# display.net
KiCad netlist of a schematic drawn in Altium Designer
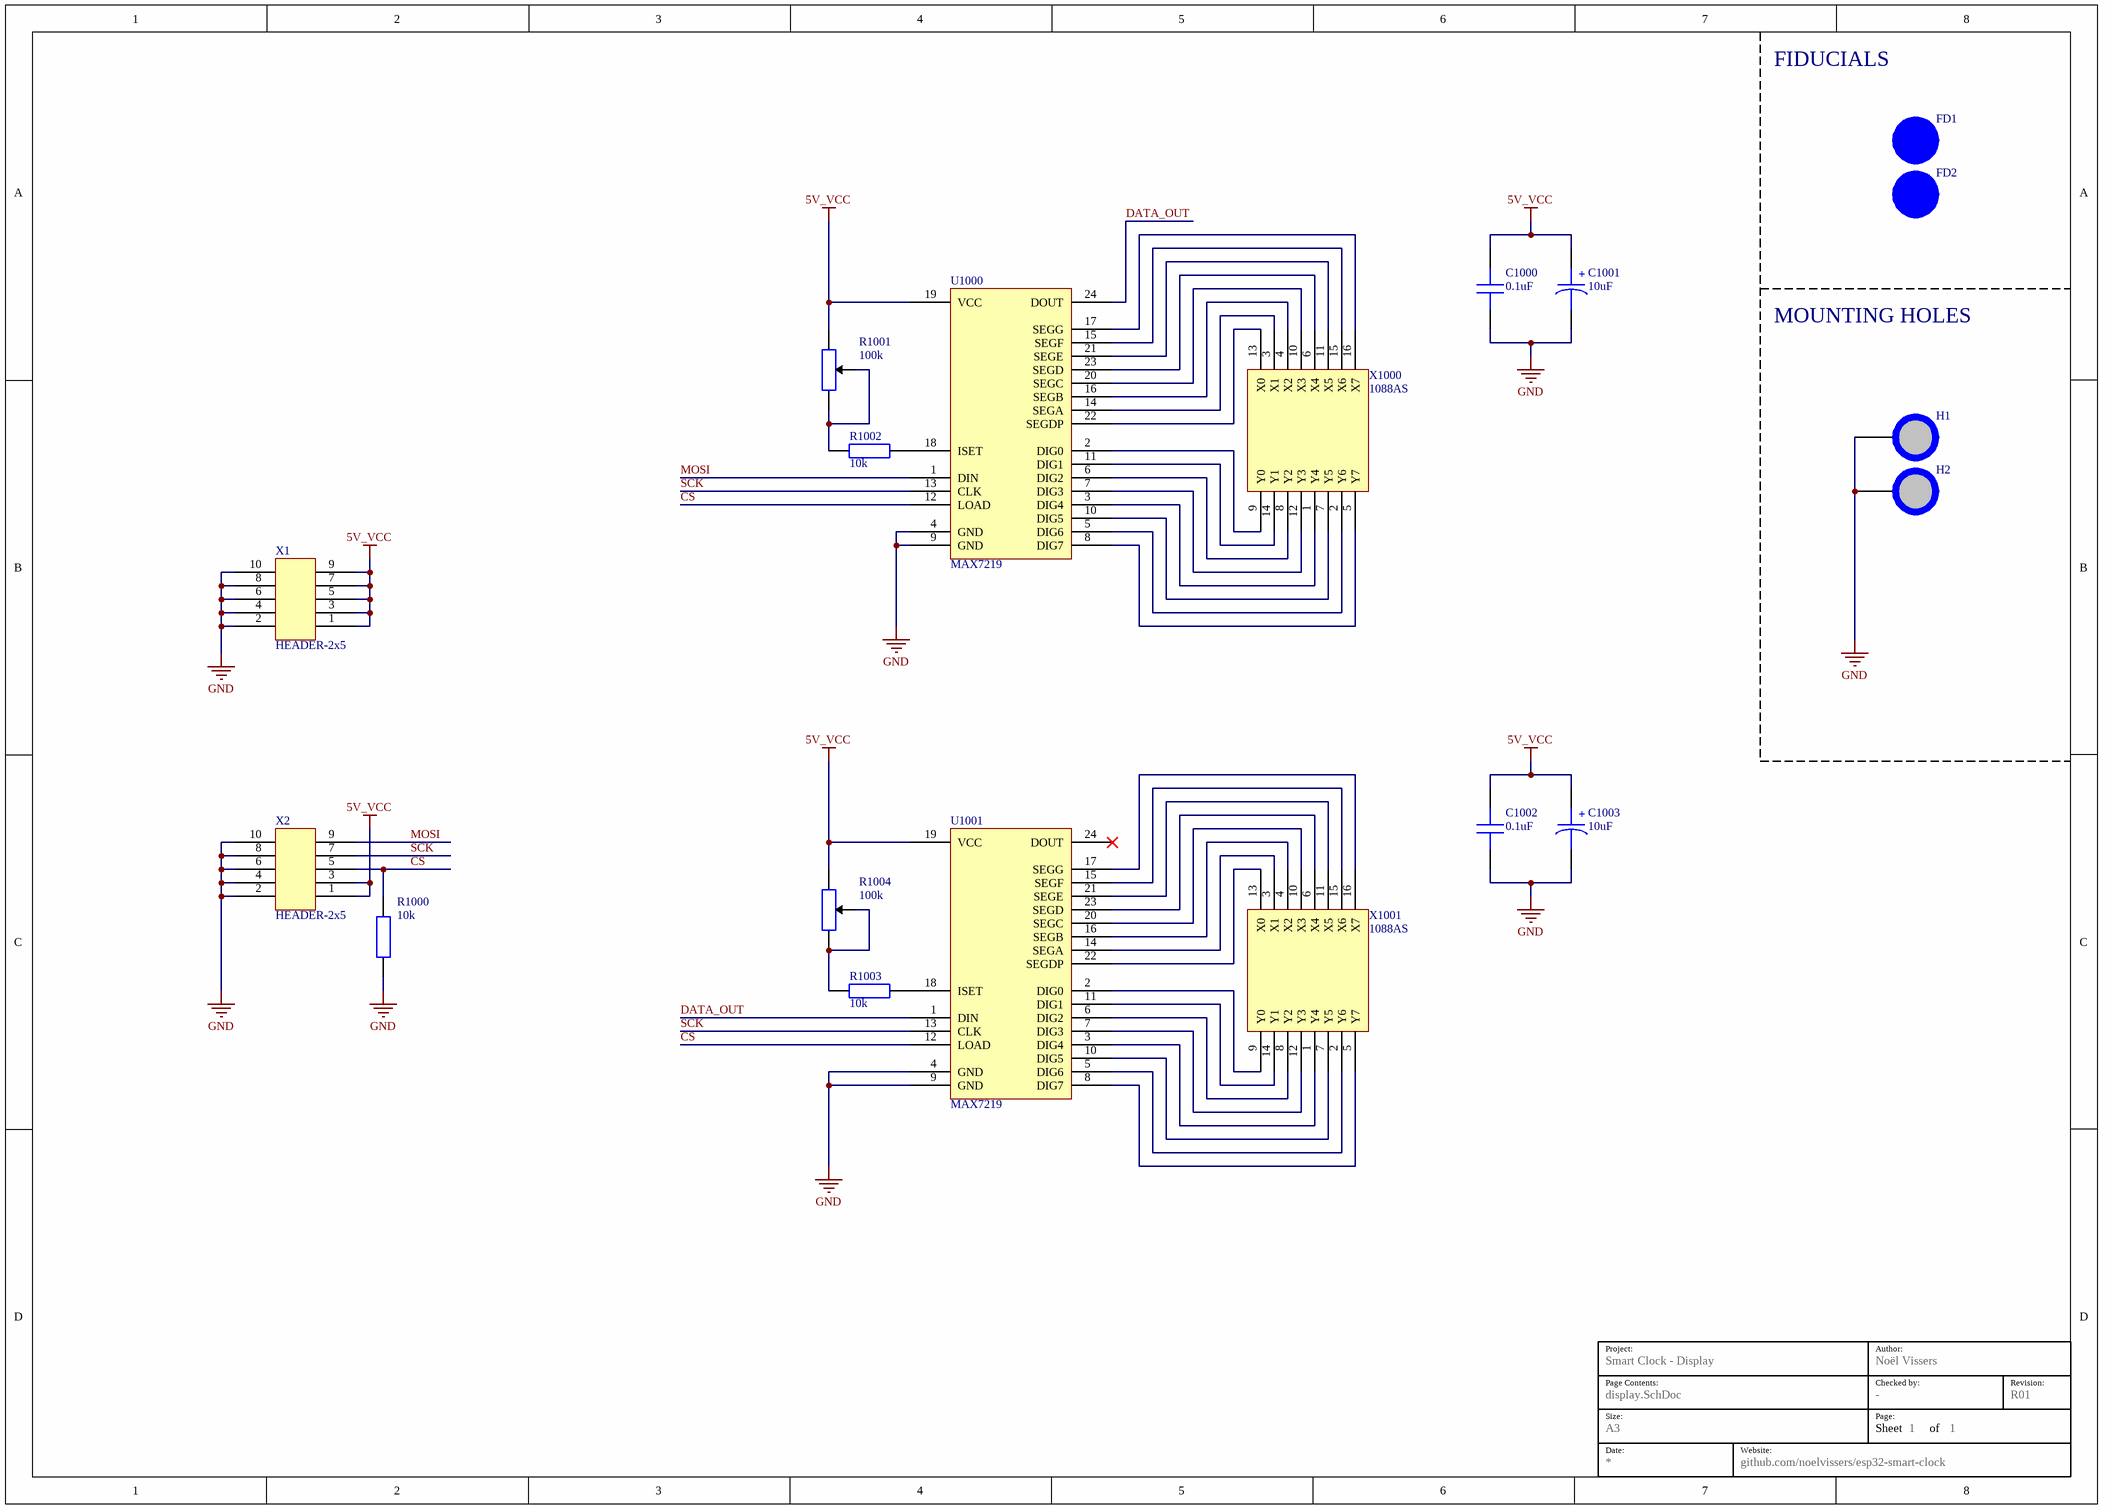
[diagram p0: display.SchDoc]

(export (version "E")
  (design (tool "Eeschema 10.0.6"))
  (components
    (comp (ref "*")
      (value "TITLE BLOCK")
      (fields (field (name "SIZE") "A3"))
      (libsource (lib "smart-clock-lib") (part "TITLE BLOCK"))
    )
    (comp (ref "C1000")
      (value "0.1uF")
      (footprint "TH-CAPACITOR - ANGLE")
      (description "GENERIC CAPACITOR")
      (libsource (lib "smart-clock-lib") (part "CAPACITOR"))
    )
    (comp (ref "C1001")
      (value "10uF")
      (footprint "TH-CAPACITOR - POL - ANGLE")
      (description "POLARIZED CAPACITOR")
      (libsource (lib "smart-clock-lib") (part "CAPACITOR POL"))
    )
    (comp (ref "C1002")
      (value "0.1uF")
      (footprint "TH-CAPACITOR - ANGLE")
      (description "GENERIC CAPACITOR")
      (libsource (lib "smart-clock-lib") (part "CAPACITOR"))
    )
    (comp (ref "C1003")
      (value "10uF")
      (footprint "TH-CAPACITOR - POL - ANGLE")
      (description "POLARIZED CAPACITOR")
      (libsource (lib "smart-clock-lib") (part "CAPACITOR POL"))
    )
    (comp (ref "FD1")
      (value "FD")
      (footprint "FD")
      (description "FIDUCIAL MARKER")
      (libsource (lib "smart-clock-lib") (part "FD"))
    )
    (comp (ref "FD2")
      (value "FD")
      (footprint "FD")
      (description "FIDUCIAL MARKER")
      (libsource (lib "smart-clock-lib") (part "FD"))
    )
    (comp (ref "H1")
      (value "SIZE")
      (footprint "HOLE")
      (description "M3 MOUNTING HOLE WITH SCREW AND SPACER")
      (libsource (lib "smart-clock-lib") (part "MOUNTING-HOLE"))
    )
    (comp (ref "H2")
      (value "SIZE")
      (footprint "HOLE")
      (description "M3 MOUNTING HOLE WITH SCREW AND SPACER")
      (libsource (lib "smart-clock-lib") (part "MOUNTING-HOLE"))
    )
    (comp (ref "R1000")
      (value "10k")
      (footprint "AXIAL RESISTOR")
      (description "GENERIC RESISTOR")
      (libsource (lib "") (part "RESISTOR_1"))
    )
    (comp (ref "R1001")
      (value "100k")
      (footprint "POTENTIOMETER")
      (description "POTMETER")
      (libsource (lib "smart-clock-lib") (part "POTMETER"))
    )
    (comp (ref "R1002")
      (value "10k")
      (footprint "AXIAL RESISTOR")
      (description "GENERIC RESISTOR")
      (libsource (lib "smart-clock-lib") (part "RESISTOR"))
    )
    (comp (ref "R1003")
      (value "10k")
      (footprint "AXIAL RESISTOR")
      (description "GENERIC RESISTOR")
      (libsource (lib "smart-clock-lib") (part "RESISTOR"))
    )
    (comp (ref "R1004")
      (value "100k")
      (footprint "POTENTIOMETER")
      (description "POTMETER")
      (libsource (lib "smart-clock-lib") (part "POTMETER"))
    )
    (comp (ref "U1000")
      (value "MAX7219")
      (footprint "DIP-24 WITH SOCKET")
      (description "IC DRVR 7 SEGMNT 8 DIGIT 24SOIC")
      (fields
        (field (name "MF") "Maxim Integrated")
        (field (name "DIGI-KEY_PART_NUMBER") "MAX7219CWG+TCT-ND")
      )
      (libsource (lib "smart-clock-lib") (part "MAX7219"))
    )
    (comp (ref "U1001")
      (value "MAX7219")
      (footprint "DIP-24 WITH SOCKET")
      (description "IC DRVR 7 SEGMNT 8 DIGIT 24SOIC")
      (fields
        (field (name "MF") "Maxim Integrated")
        (field (name "DIGI-KEY_PART_NUMBER") "MAX7219CWG+TCT-ND")
      )
      (libsource (lib "smart-clock-lib") (part "MAX7219"))
    )
    (comp (ref "X1")
      (value "HEADER-2x5")
      (footprint "HEADER-2x5-MALE")
      (description "2.54mm HEADER 2x5")
      (libsource (lib "smart-clock-lib") (part "HEADER-2x5"))
    )
    (comp (ref "X2")
      (value "HEADER-2x5")
      (footprint "HEADER-2x5-MALE")
      (description "2.54mm HEADER 2x5")
      (libsource (lib "smart-clock-lib") (part "HEADER-2x5"))
    )
    (comp (ref "X1000")
      (value "1088AS")
      (footprint "1088AS-DOT-MATRIX-8x8")
      (description "8x8 DOT MATRIX LED DISPLAY")
      (libsource (lib "smart-clock-lib") (part "1088AS-DOT-MATRIX"))
    )
    (comp (ref "X1001")
      (value "1088AS")
      (footprint "1088AS-DOT-MATRIX-8x8")
      (description "8x8 DOT MATRIX LED DISPLAY")
      (libsource (lib "smart-clock-lib") (part "1088AS-DOT-MATRIX"))
    )
  )
  (nets
    (net (code "1") (name "/CS") (class "Default")
      (node (ref "R1000") (pin "1") (pinfunction "1_1") (pintype "passive"))
      (node (ref "U1000") (pin "12") (pinfunction "LOAD_12") (pintype "passive"))
      (node (ref "U1001") (pin "12") (pinfunction "LOAD_12") (pintype "passive"))
      (node (ref "X2") (pin "5") (pinfunction "5_5") (pintype "passive"))
    )
    (net (code "2") (name "/DATA_OUT") (class "Default")
      (node (ref "U1000") (pin "24") (pinfunction "DOUT_24") (pintype "passive"))
      (node (ref "U1001") (pin "1") (pinfunction "DIN_1") (pintype "passive"))
    )
    (net (code "3") (name "/MOSI") (class "Default")
      (node (ref "U1000") (pin "1") (pinfunction "DIN_1") (pintype "passive"))
      (node (ref "X2") (pin "9") (pinfunction "9_9") (pintype "passive"))
    )
    (net (code "4") (name "/SCK") (class "Default")
      (node (ref "U1000") (pin "13") (pinfunction "CLK_13") (pintype "passive"))
      (node (ref "U1001") (pin "13") (pinfunction "CLK_13") (pintype "passive"))
      (node (ref "X2") (pin "7") (pinfunction "7_7") (pintype "passive"))
    )
    (net (code "5") (name "5V_VCC") (class "Default")
      (node (ref "C1000") (pin "1") (pinfunction "1_1") (pintype "passive"))
      (node (ref "C1001") (pin "2") (pinfunction "2_2") (pintype "passive"))
      (node (ref "C1002") (pin "1") (pinfunction "1_1") (pintype "passive"))
      (node (ref "C1003") (pin "2") (pinfunction "2_2") (pintype "passive"))
      (node (ref "R1001") (pin "1") (pinfunction "1_1") (pintype "passive"))
      (node (ref "R1004") (pin "1") (pinfunction "1_1") (pintype "passive"))
      (node (ref "U1000") (pin "19") (pinfunction "VCC_19") (pintype "passive"))
      (node (ref "U1001") (pin "19") (pinfunction "VCC_19") (pintype "passive"))
      (node (ref "X1") (pin "1") (pinfunction "1_1") (pintype "passive"))
      (node (ref "X1") (pin "3") (pinfunction "3_3") (pintype "passive"))
      (node (ref "X1") (pin "5") (pinfunction "5_5") (pintype "passive"))
      (node (ref "X1") (pin "7") (pinfunction "7_7") (pintype "passive"))
      (node (ref "X1") (pin "9") (pinfunction "9_9") (pintype "passive"))
      (node (ref "X2") (pin "1") (pinfunction "1_1") (pintype "passive"))
      (node (ref "X2") (pin "3") (pinfunction "3_3") (pintype "passive"))
    )
    (net (code "6") (name "GND") (class "Default")
      (node (ref "C1000") (pin "2") (pinfunction "2_2") (pintype "passive"))
      (node (ref "C1001") (pin "1") (pinfunction "1_1") (pintype "passive"))
      (node (ref "C1002") (pin "2") (pinfunction "2_2") (pintype "passive"))
      (node (ref "C1003") (pin "1") (pinfunction "1_1") (pintype "passive"))
      (node (ref "H1") (pin "1") (pintype "passive"))
      (node (ref "H2") (pin "1") (pintype "passive"))
      (node (ref "R1000") (pin "2") (pinfunction "2_2") (pintype "passive"))
      (node (ref "U1000") (pin "4") (pinfunction "GND_4") (pintype "passive"))
      (node (ref "U1000") (pin "9") (pinfunction "GND_9") (pintype "passive"))
      (node (ref "U1001") (pin "4") (pinfunction "GND_4") (pintype "passive"))
      (node (ref "U1001") (pin "9") (pinfunction "GND_9") (pintype "passive"))
      (node (ref "X1") (pin "10") (pinfunction "10_10") (pintype "passive"))
      (node (ref "X1") (pin "2") (pinfunction "2_2") (pintype "passive"))
      (node (ref "X1") (pin "4") (pinfunction "4_4") (pintype "passive"))
      (node (ref "X1") (pin "6") (pinfunction "6_6") (pintype "passive"))
      (node (ref "X1") (pin "8") (pinfunction "8_8") (pintype "passive"))
      (node (ref "X2") (pin "10") (pinfunction "10_10") (pintype "passive"))
      (node (ref "X2") (pin "2") (pinfunction "2_2") (pintype "passive"))
      (node (ref "X2") (pin "4") (pinfunction "4_4") (pintype "passive"))
      (node (ref "X2") (pin "6") (pinfunction "6_6") (pintype "passive"))
      (node (ref "X2") (pin "8") (pinfunction "8_8") (pintype "passive"))
    )
    (net (code "7") (name "Net-(R1001-Pad2)") (class "Default")
      (node (ref "R1001") (pin "2") (pinfunction "2_2") (pintype "passive"))
      (node (ref "R1001") (pin "3") (pinfunction "3_3") (pintype "passive"))
      (node (ref "R1002") (pin "1") (pinfunction "1_1") (pintype "passive"))
    )
    (net (code "8") (name "Net-(R1003-Pad1)") (class "Default")
      (node (ref "R1003") (pin "1") (pinfunction "1_1") (pintype "passive"))
      (node (ref "R1004") (pin "2") (pinfunction "2_2") (pintype "passive"))
      (node (ref "R1004") (pin "3") (pinfunction "3_3") (pintype "passive"))
    )
    (net (code "9") (name "Net-(U1000-DIG0)") (class "Default")
      (node (ref "U1000") (pin "2") (pinfunction "DIG0_2") (pintype "passive"))
      (node (ref "X1000") (pin "9") (pinfunction "Y0_9") (pintype "passive"))
    )
    (net (code "10") (name "Net-(U1000-DIG1)") (class "Default")
      (node (ref "U1000") (pin "11") (pinfunction "DIG1_11") (pintype "passive"))
      (node (ref "X1000") (pin "14") (pinfunction "Y1_14") (pintype "passive"))
    )
    (net (code "11") (name "Net-(U1000-DIG2)") (class "Default")
      (node (ref "U1000") (pin "6") (pinfunction "DIG2_6") (pintype "passive"))
      (node (ref "X1000") (pin "8") (pinfunction "Y2_8") (pintype "passive"))
    )
    (net (code "12") (name "Net-(U1000-DIG3)") (class "Default")
      (node (ref "U1000") (pin "7") (pinfunction "DIG3_7") (pintype "passive"))
      (node (ref "X1000") (pin "12") (pinfunction "Y3_12") (pintype "passive"))
    )
    (net (code "13") (name "Net-(U1000-DIG4)") (class "Default")
      (node (ref "U1000") (pin "3") (pinfunction "DIG4_3") (pintype "passive"))
      (node (ref "X1000") (pin "1") (pinfunction "Y4_1") (pintype "passive"))
    )
    (net (code "14") (name "Net-(U1000-DIG5)") (class "Default")
      (node (ref "U1000") (pin "10") (pinfunction "DIG5_10") (pintype "passive"))
      (node (ref "X1000") (pin "7") (pinfunction "Y5_7") (pintype "passive"))
    )
    (net (code "15") (name "Net-(U1000-DIG6)") (class "Default")
      (node (ref "U1000") (pin "5") (pinfunction "DIG6_5") (pintype "passive"))
      (node (ref "X1000") (pin "2") (pinfunction "Y6_2") (pintype "passive"))
    )
    (net (code "16") (name "Net-(U1000-DIG7)") (class "Default")
      (node (ref "U1000") (pin "8") (pinfunction "DIG7_8") (pintype "passive"))
      (node (ref "X1000") (pin "5") (pinfunction "Y7_5") (pintype "passive"))
    )
    (net (code "17") (name "Net-(U1000-ISET)") (class "Default")
      (node (ref "R1002") (pin "2") (pinfunction "2_2") (pintype "passive"))
      (node (ref "U1000") (pin "18") (pinfunction "ISET_18") (pintype "passive"))
    )
    (net (code "18") (name "Net-(U1000-SEGA)") (class "Default")
      (node (ref "U1000") (pin "14") (pinfunction "SEGA_14") (pintype "passive"))
      (node (ref "X1000") (pin "3") (pinfunction "X1_3") (pintype "passive"))
    )
    (net (code "19") (name "Net-(U1000-SEGB)") (class "Default")
      (node (ref "U1000") (pin "16") (pinfunction "SEGB_16") (pintype "passive"))
      (node (ref "X1000") (pin "4") (pinfunction "X2_4") (pintype "passive"))
    )
    (net (code "20") (name "Net-(U1000-SEGC)") (class "Default")
      (node (ref "U1000") (pin "20") (pinfunction "SEGC_20") (pintype "passive"))
      (node (ref "X1000") (pin "10") (pinfunction "X3_10") (pintype "passive"))
    )
    (net (code "21") (name "Net-(U1000-SEGD)") (class "Default")
      (node (ref "U1000") (pin "23") (pinfunction "SEGD_23") (pintype "passive"))
      (node (ref "X1000") (pin "6") (pinfunction "X4_6") (pintype "passive"))
    )
    (net (code "22") (name "Net-(U1000-SEGDP)") (class "Default")
      (node (ref "U1000") (pin "22") (pinfunction "SEGDP_22") (pintype "passive"))
      (node (ref "X1000") (pin "13") (pinfunction "X0_13") (pintype "passive"))
    )
    (net (code "23") (name "Net-(U1000-SEGE)") (class "Default")
      (node (ref "U1000") (pin "21") (pinfunction "SEGE_21") (pintype "passive"))
      (node (ref "X1000") (pin "11") (pinfunction "X5_11") (pintype "passive"))
    )
    (net (code "24") (name "Net-(U1000-SEGF)") (class "Default")
      (node (ref "U1000") (pin "15") (pinfunction "SEGF_15") (pintype "passive"))
      (node (ref "X1000") (pin "15") (pinfunction "X6_15") (pintype "passive"))
    )
    (net (code "25") (name "Net-(U1000-SEGG)") (class "Default")
      (node (ref "U1000") (pin "17") (pinfunction "SEGG_17") (pintype "passive"))
      (node (ref "X1000") (pin "16") (pinfunction "X7_16") (pintype "passive"))
    )
    (net (code "26") (name "Net-(U1001-DIG0)") (class "Default")
      (node (ref "U1001") (pin "2") (pinfunction "DIG0_2") (pintype "passive"))
      (node (ref "X1001") (pin "9") (pinfunction "Y0_9") (pintype "passive"))
    )
    (net (code "27") (name "Net-(U1001-DIG1)") (class "Default")
      (node (ref "U1001") (pin "11") (pinfunction "DIG1_11") (pintype "passive"))
      (node (ref "X1001") (pin "14") (pinfunction "Y1_14") (pintype "passive"))
    )
    (net (code "28") (name "Net-(U1001-DIG2)") (class "Default")
      (node (ref "U1001") (pin "6") (pinfunction "DIG2_6") (pintype "passive"))
      (node (ref "X1001") (pin "8") (pinfunction "Y2_8") (pintype "passive"))
    )
    (net (code "29") (name "Net-(U1001-DIG3)") (class "Default")
      (node (ref "U1001") (pin "7") (pinfunction "DIG3_7") (pintype "passive"))
      (node (ref "X1001") (pin "12") (pinfunction "Y3_12") (pintype "passive"))
    )
    (net (code "30") (name "Net-(U1001-DIG4)") (class "Default")
      (node (ref "U1001") (pin "3") (pinfunction "DIG4_3") (pintype "passive"))
      (node (ref "X1001") (pin "1") (pinfunction "Y4_1") (pintype "passive"))
    )
    (net (code "31") (name "Net-(U1001-DIG5)") (class "Default")
      (node (ref "U1001") (pin "10") (pinfunction "DIG5_10") (pintype "passive"))
      (node (ref "X1001") (pin "7") (pinfunction "Y5_7") (pintype "passive"))
    )
    (net (code "32") (name "Net-(U1001-DIG6)") (class "Default")
      (node (ref "U1001") (pin "5") (pinfunction "DIG6_5") (pintype "passive"))
      (node (ref "X1001") (pin "2") (pinfunction "Y6_2") (pintype "passive"))
    )
    (net (code "33") (name "Net-(U1001-DIG7)") (class "Default")
      (node (ref "U1001") (pin "8") (pinfunction "DIG7_8") (pintype "passive"))
      (node (ref "X1001") (pin "5") (pinfunction "Y7_5") (pintype "passive"))
    )
    (net (code "34") (name "Net-(U1001-ISET)") (class "Default")
      (node (ref "R1003") (pin "2") (pinfunction "2_2") (pintype "passive"))
      (node (ref "U1001") (pin "18") (pinfunction "ISET_18") (pintype "passive"))
    )
    (net (code "35") (name "Net-(U1001-SEGA)") (class "Default")
      (node (ref "U1001") (pin "14") (pinfunction "SEGA_14") (pintype "passive"))
      (node (ref "X1001") (pin "3") (pinfunction "X1_3") (pintype "passive"))
    )
    (net (code "36") (name "Net-(U1001-SEGB)") (class "Default")
      (node (ref "U1001") (pin "16") (pinfunction "SEGB_16") (pintype "passive"))
      (node (ref "X1001") (pin "4") (pinfunction "X2_4") (pintype "passive"))
    )
    (net (code "37") (name "Net-(U1001-SEGC)") (class "Default")
      (node (ref "U1001") (pin "20") (pinfunction "SEGC_20") (pintype "passive"))
      (node (ref "X1001") (pin "10") (pinfunction "X3_10") (pintype "passive"))
    )
    (net (code "38") (name "Net-(U1001-SEGD)") (class "Default")
      (node (ref "U1001") (pin "23") (pinfunction "SEGD_23") (pintype "passive"))
      (node (ref "X1001") (pin "6") (pinfunction "X4_6") (pintype "passive"))
    )
    (net (code "39") (name "Net-(U1001-SEGDP)") (class "Default")
      (node (ref "U1001") (pin "22") (pinfunction "SEGDP_22") (pintype "passive"))
      (node (ref "X1001") (pin "13") (pinfunction "X0_13") (pintype "passive"))
    )
    (net (code "40") (name "Net-(U1001-SEGE)") (class "Default")
      (node (ref "U1001") (pin "21") (pinfunction "SEGE_21") (pintype "passive"))
      (node (ref "X1001") (pin "11") (pinfunction "X5_11") (pintype "passive"))
    )
    (net (code "41") (name "Net-(U1001-SEGF)") (class "Default")
      (node (ref "U1001") (pin "15") (pinfunction "SEGF_15") (pintype "passive"))
      (node (ref "X1001") (pin "15") (pinfunction "X6_15") (pintype "passive"))
    )
    (net (code "42") (name "Net-(U1001-SEGG)") (class "Default")
      (node (ref "U1001") (pin "17") (pinfunction "SEGG_17") (pintype "passive"))
      (node (ref "X1001") (pin "16") (pinfunction "X7_16") (pintype "passive"))
    )
    (net (code "43") (name "unconnected-(FD1-Pad1)") (class "Default")
      (node (ref "FD1") (pin "1") (pinfunction "1_1") (pintype "passive"))
    )
    (net (code "44") (name "unconnected-(FD2-Pad1)") (class "Default")
      (node (ref "FD2") (pin "1") (pinfunction "1_1") (pintype "passive"))
    )
    (net (code "45") (name "unconnected-(U1001-DOUT-Pad24)") (class "Default")
      (node (ref "U1001") (pin "24") (pinfunction "DOUT_24") (pintype "passive+no_connect"))
    )
  )
)
